# licthla.net
KiCad netlist of a schematic drawn in EAGLE
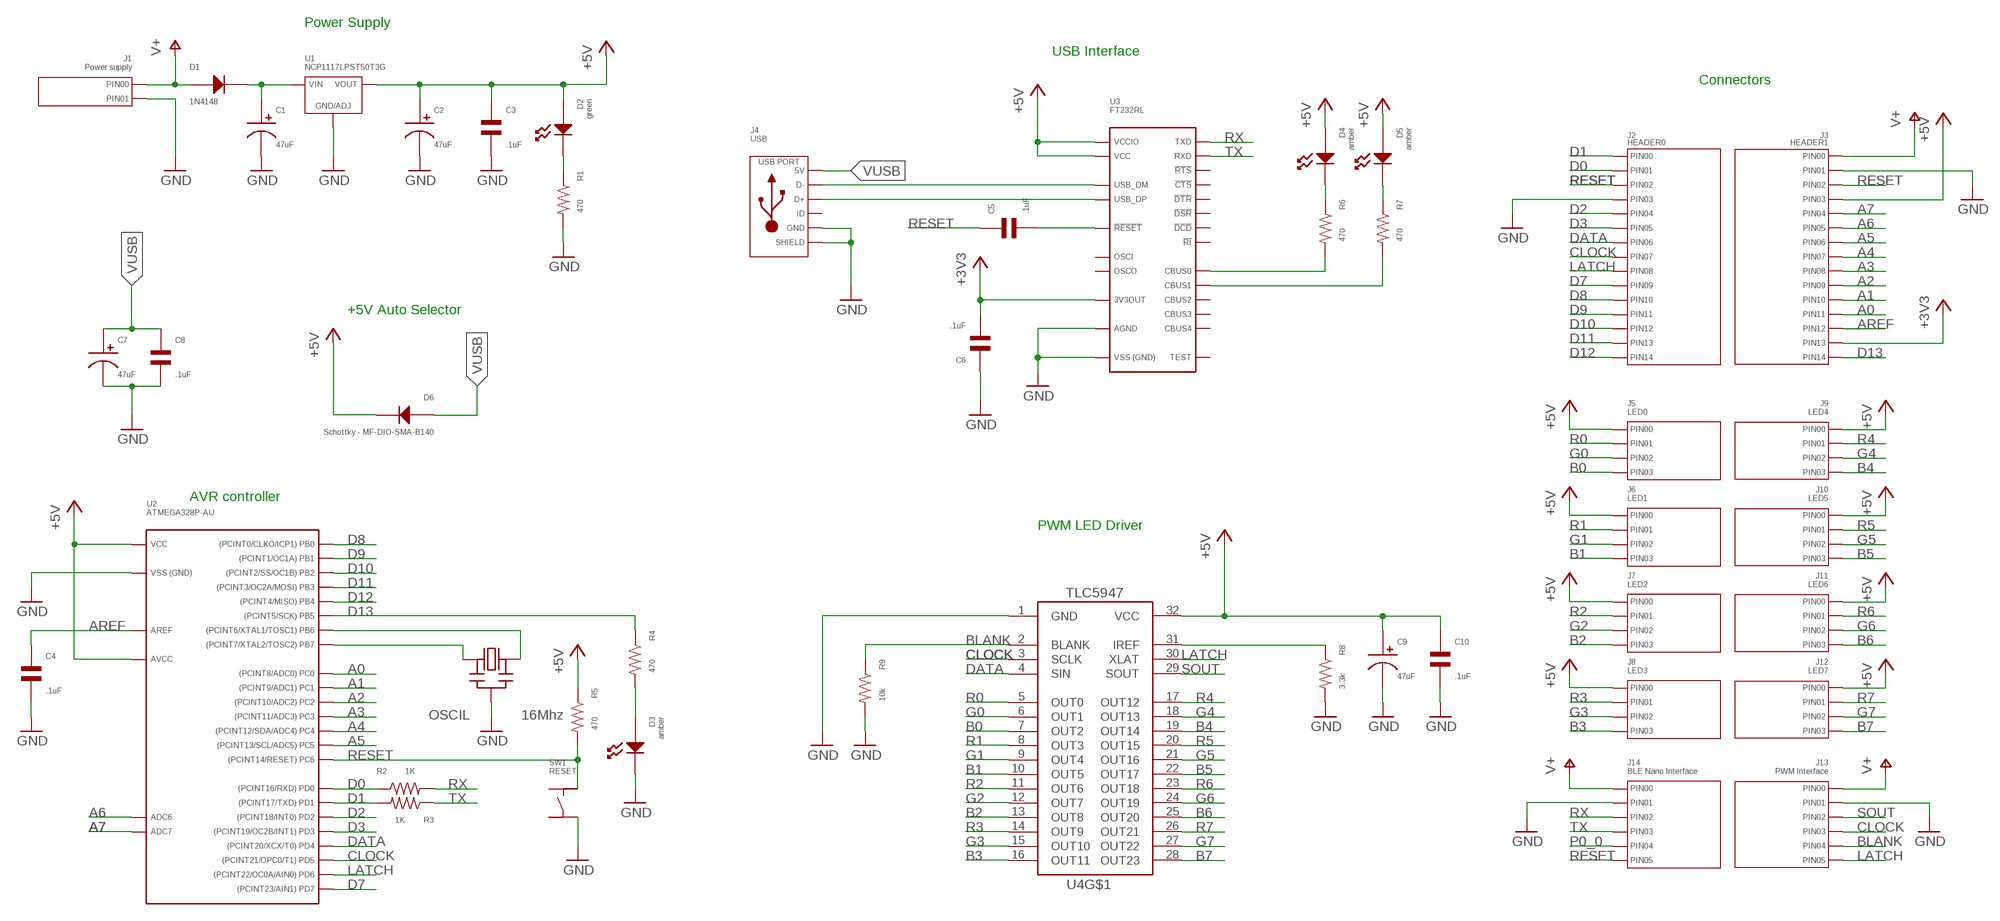
[diagram p0: schematic, sheet 1]

(export (version "E")
  (design (tool "Eeschema 10.0.6"))
  (components
    (comp (ref "C1")
      (value "47uF")
      (footprint "eagle-import:CP6.3MM")
      (libsource (lib "eagle-import") (part "CAPACITOR_P_6.3MM"))
    )
    (comp (ref "C2")
      (value "47uF")
      (footprint "eagle-import:CP6.3MM")
      (libsource (lib "eagle-import") (part "CAPACITOR_P_6.3MM"))
    )
    (comp (ref "C3")
      (value ".1uF")
      (footprint "eagle-import:C0402")
      (libsource (lib "eagle-import") (part "CAPACITOR_NP_0402"))
    )
    (comp (ref "C4")
      (value ".1uF")
      (footprint "eagle-import:C0402")
      (libsource (lib "eagle-import") (part "CAPACITOR_NP_0402"))
    )
    (comp (ref "C5")
      (value ".1uF")
      (footprint "eagle-import:C0402")
      (libsource (lib "eagle-import") (part "CAPACITOR_NP_0402"))
    )
    (comp (ref "C6")
      (value ".1uF")
      (footprint "eagle-import:C0402")
      (libsource (lib "eagle-import") (part "CAPACITOR_NP_0402"))
    )
    (comp (ref "C7")
      (value "47uF")
      (footprint "eagle-import:CP6.3MM")
      (libsource (lib "eagle-import") (part "CAPACITOR_P_6.3MM"))
    )
    (comp (ref "C8")
      (value ".1uF")
      (footprint "eagle-import:C0402")
      (libsource (lib "eagle-import") (part "CAPACITOR_NP_0402"))
    )
    (comp (ref "C9")
      (value "47uF")
      (footprint "eagle-import:CP6.3MM")
      (libsource (lib "eagle-import") (part "CAPACITOR_P_6.3MM"))
    )
    (comp (ref "C10")
      (value ".1uF")
      (footprint "eagle-import:C0402")
      (libsource (lib "eagle-import") (part "CAPACITOR_NP_0402"))
    )
    (comp (ref "D1")
      (value "1N4148")
      (footprint "eagle-import:SOD-123")
      (libsource (lib "eagle-import") (part "DIODE_SOD-123"))
    )
    (comp (ref "D2")
      (value "green")
      (footprint "eagle-import:LED0805")
      (libsource (lib "eagle-import") (part "LED_SINGLE_0805"))
    )
    (comp (ref "D3")
      (value "amber")
      (footprint "eagle-import:LED0805")
      (libsource (lib "eagle-import") (part "LED_SINGLE_0805"))
    )
    (comp (ref "D4")
      (value "amber")
      (footprint "eagle-import:LED0805")
      (libsource (lib "eagle-import") (part "LED_SINGLE_0805"))
    )
    (comp (ref "D5")
      (value "amber")
      (footprint "eagle-import:LED0805")
      (libsource (lib "eagle-import") (part "LED_SINGLE_0805"))
    )
    (comp (ref "D6")
      (value "Schottky - MF-DIO-SMA-B140")
      (footprint "eagle-import:SMA")
      (libsource (lib "eagle-import") (part "DIODE_SMA"))
    )
    (comp (ref "J1")
      (value "Power supply")
      (footprint "eagle-import:PTH_2.54MM_01X02")
      (libsource (lib "eagle-import") (part "HEADER_01X02_PTH_2.54MM"))
    )
    (comp (ref "J2")
      (value "HEADER0")
      (footprint "eagle-import:PTH_2.54MM_01X15")
      (libsource (lib "eagle-import") (part "HEADER_01X15_PTH_2.54MM"))
    )
    (comp (ref "J3")
      (value "HEADER1")
      (footprint "eagle-import:PTH_2.54MM_01X15")
      (libsource (lib "eagle-import") (part "HEADER_01X15_PTH_2.54MM"))
    )
    (comp (ref "J4")
      (value "USB")
      (footprint "eagle-import:MICROUSB-RIGHT")
      (libsource (lib "eagle-import") (part "USB_MICRO_RIGHT"))
    )
    (comp (ref "J5")
      (value "LED0")
      (footprint "eagle-import:PTH_2.54MM_01X04")
      (libsource (lib "eagle-import") (part "HEADER_01X04_PTH_2.54MM"))
    )
    (comp (ref "J6")
      (value "LED1")
      (footprint "eagle-import:PTH_2.54MM_01X04")
      (libsource (lib "eagle-import") (part "HEADER_01X04_PTH_2.54MM"))
    )
    (comp (ref "J7")
      (value "LED2")
      (footprint "eagle-import:PTH_2.54MM_01X04")
      (libsource (lib "eagle-import") (part "HEADER_01X04_PTH_2.54MM"))
    )
    (comp (ref "J8")
      (value "LED3")
      (footprint "eagle-import:PTH_2.54MM_01X04")
      (libsource (lib "eagle-import") (part "HEADER_01X04_PTH_2.54MM"))
    )
    (comp (ref "J9")
      (value "LED4")
      (footprint "eagle-import:PTH_2.54MM_01X04")
      (libsource (lib "eagle-import") (part "HEADER_01X04_PTH_2.54MM"))
    )
    (comp (ref "J10")
      (value "LED5")
      (footprint "eagle-import:PTH_2.54MM_01X04")
      (libsource (lib "eagle-import") (part "HEADER_01X04_PTH_2.54MM"))
    )
    (comp (ref "J11")
      (value "LED6")
      (footprint "eagle-import:PTH_2.54MM_01X04")
      (libsource (lib "eagle-import") (part "HEADER_01X04_PTH_2.54MM"))
    )
    (comp (ref "J12")
      (value "LED7")
      (footprint "eagle-import:PTH_2.54MM_01X04")
      (libsource (lib "eagle-import") (part "HEADER_01X04_PTH_2.54MM"))
    )
    (comp (ref "J13")
      (value "PWM Interface")
      (footprint "eagle-import:PTH_2.54MM_01X06")
      (libsource (lib "eagle-import") (part "HEADER_01X06_PTH_2.54MM"))
    )
    (comp (ref "J14")
      (value "BLE Nano Interface")
      (footprint "eagle-import:PTH_2.54MM_01X06")
      (libsource (lib "eagle-import") (part "HEADER_01X06_PTH_2.54MM"))
    )
    (comp (ref "OSCIL")
      (value "16Mhz")
      (footprint "eagle-import:AWCSR")
      (libsource (lib "eagle-import") (part "CERMOSCILL-AWCSR"))
    )
    (comp (ref "R1")
      (value "470")
      (footprint "eagle-import:R0805")
      (libsource (lib "eagle-import") (part "RESISTOR_0805"))
    )
    (comp (ref "R2")
      (value "1K")
      (footprint "eagle-import:R0805")
      (libsource (lib "eagle-import") (part "RESISTOR_0805"))
    )
    (comp (ref "R3")
      (value "1K")
      (footprint "eagle-import:R0805")
      (libsource (lib "eagle-import") (part "RESISTOR_0805"))
    )
    (comp (ref "R4")
      (value "470")
      (footprint "eagle-import:R0805")
      (libsource (lib "eagle-import") (part "RESISTOR_0805"))
    )
    (comp (ref "R5")
      (value "470")
      (footprint "eagle-import:R0805")
      (libsource (lib "eagle-import") (part "RESISTOR_0805"))
    )
    (comp (ref "R6")
      (value "470")
      (footprint "eagle-import:R0805")
      (libsource (lib "eagle-import") (part "RESISTOR_0805"))
    )
    (comp (ref "R7")
      (value "470")
      (footprint "eagle-import:R0805")
      (libsource (lib "eagle-import") (part "RESISTOR_0805"))
    )
    (comp (ref "R8")
      (value "3.3k")
      (footprint "eagle-import:R0805")
      (libsource (lib "eagle-import") (part "RESISTOR_0805"))
    )
    (comp (ref "R9")
      (value "10k")
      (footprint "eagle-import:R0805")
      (libsource (lib "eagle-import") (part "RESISTOR_0805"))
    )
    (comp (ref "SW1")
      (value "RESET")
      (footprint "eagle-import:TACT6MM")
      (libsource (lib "eagle-import") (part "TACT_6MM"))
    )
    (comp (ref "U1")
      (value "NCP1117LPST50T3G")
      (footprint "eagle-import:SOT-223-3")
      (libsource (lib "eagle-import") (part "NCP1117LPST50T3G"))
    )
    (comp (ref "U2")
      (value "ATMEGA328P-AU")
      (footprint "eagle-import:TQFP32")
      (libsource (lib "eagle-import") (part "ATMEGA328P-AU"))
    )
    (comp (ref "U3")
      (value "FT232RL")
      (footprint "eagle-import:SSOP28")
      (libsource (lib "eagle-import") (part "FT232RL"))
    )
    (comp (ref "U4")
      (value "TLC5947-DAP")
      (footprint "eagle-import:HTSSOP32DAP")
      (libsource (lib "eagle-import") (part "TLC5947-DAP"))
    )
  )
  (nets
    (net (code "1") (name "+3V3") (class "Default")
      (node (ref "C6") (pin "P$2") (pinfunction "P$2_P$2") (pintype "passive"))
      (node (ref "J3") (pin "P$14") (pinfunction "PIN13_P$14") (pintype "bidirectional"))
      (node (ref "U3") (pin "P$17") (pinfunction "3V3OUT_P$17") (pintype "bidirectional"))
    )
    (net (code "2") (name "+5V") (class "Default")
      (node (ref "C10") (pin "P$1") (pinfunction "P$1_P$1") (pintype "passive"))
      (node (ref "C2") (pin "P$1") (pinfunction "P$1_P$1") (pintype "passive"))
      (node (ref "C3") (pin "P$1") (pinfunction "P$1_P$1") (pintype "passive"))
      (node (ref "C9") (pin "P$1") (pinfunction "P$1_P$1") (pintype "passive"))
      (node (ref "D2") (pin "ANODE") (pinfunction "ANODE_ANODE") (pintype "power_in"))
      (node (ref "D4") (pin "ANODE") (pinfunction "ANODE_ANODE") (pintype "power_in"))
      (node (ref "D5") (pin "ANODE") (pinfunction "ANODE_ANODE") (pintype "power_in"))
      (node (ref "D6") (pin "CATHODE") (pinfunction "CATHODE_CATHODE") (pintype "bidirectional"))
      (node (ref "J10") (pin "P$1") (pinfunction "PIN0_P$1") (pintype "bidirectional"))
      (node (ref "J11") (pin "P$1") (pinfunction "PIN0_P$1") (pintype "bidirectional"))
      (node (ref "J12") (pin "P$1") (pinfunction "PIN0_P$1") (pintype "bidirectional"))
      (node (ref "J3") (pin "P$4") (pinfunction "PIN3_P$4") (pintype "bidirectional"))
      (node (ref "J5") (pin "P$1") (pinfunction "PIN0_P$1") (pintype "bidirectional"))
      (node (ref "J6") (pin "P$1") (pinfunction "PIN0_P$1") (pintype "bidirectional"))
      (node (ref "J7") (pin "P$1") (pinfunction "PIN0_P$1") (pintype "bidirectional"))
      (node (ref "J8") (pin "P$1") (pinfunction "PIN0_P$1") (pintype "bidirectional"))
      (node (ref "J9") (pin "P$1") (pinfunction "PIN0_P$1") (pintype "bidirectional"))
      (node (ref "R5") (pin "P$1") (pinfunction "P$1_P$1") (pintype "passive"))
      (node (ref "U1") (pin "P$1") (pinfunction "VOUT_P$1") (pintype "bidirectional"))
      (node (ref "U1") (pin "P$3") (pinfunction "VOUT_P$3") (pintype "bidirectional"))
      (node (ref "U2") (pin "P$18") (pinfunction "AVCC_P$18") (pintype "power_in"))
      (node (ref "U2") (pin "P$4") (pinfunction "VCC_P$4") (pintype "power_in"))
      (node (ref "U2") (pin "P$6") (pinfunction "VCC_P$6") (pintype "power_in"))
      (node (ref "U3") (pin "P$20") (pinfunction "VCC_P$20") (pintype "bidirectional"))
      (node (ref "U3") (pin "P$4") (pinfunction "VCCIO_P$4") (pintype "bidirectional"))
      (node (ref "U4") (pin "32") (pinfunction "VCC_32") (pintype "power_in"))
    )
    (net (code "3") (name "/A0") (class "Default")
      (node (ref "J3") (pin "P$12") (pinfunction "PIN11_P$12") (pintype "bidirectional"))
      (node (ref "U2") (pin "P$23") (pinfunction "PC0_P$23") (pintype "bidirectional"))
    )
    (net (code "4") (name "/A1") (class "Default")
      (node (ref "J3") (pin "P$11") (pinfunction "PIN10_P$11") (pintype "bidirectional"))
      (node (ref "U2") (pin "P$24") (pinfunction "PC1_P$24") (pintype "bidirectional"))
    )
    (net (code "5") (name "/A2") (class "Default")
      (node (ref "J3") (pin "P$10") (pinfunction "PIN9_P$10") (pintype "bidirectional"))
      (node (ref "U2") (pin "P$25") (pinfunction "PC2_P$25") (pintype "bidirectional"))
    )
    (net (code "6") (name "/A3") (class "Default")
      (node (ref "J3") (pin "P$9") (pinfunction "PIN8_P$9") (pintype "bidirectional"))
      (node (ref "U2") (pin "P$26") (pinfunction "PC3_P$26") (pintype "bidirectional"))
    )
    (net (code "7") (name "/A4") (class "Default")
      (node (ref "J3") (pin "P$8") (pinfunction "PIN7_P$8") (pintype "bidirectional"))
      (node (ref "U2") (pin "P$27") (pinfunction "PC4_P$27") (pintype "bidirectional"))
    )
    (net (code "8") (name "/A5") (class "Default")
      (node (ref "J3") (pin "P$7") (pinfunction "PIN6_P$7") (pintype "bidirectional"))
      (node (ref "U2") (pin "P$28") (pinfunction "PC5_P$28") (pintype "bidirectional"))
    )
    (net (code "9") (name "/A6") (class "Default")
      (node (ref "J3") (pin "P$6") (pinfunction "PIN5_P$6") (pintype "bidirectional"))
      (node (ref "U2") (pin "P$19") (pinfunction "ADC6_P$19") (pintype "bidirectional"))
    )
    (net (code "10") (name "/A7") (class "Default")
      (node (ref "J3") (pin "P$5") (pinfunction "PIN4_P$5") (pintype "bidirectional"))
      (node (ref "U2") (pin "P$22") (pinfunction "ADC7_P$22") (pintype "bidirectional"))
    )
    (net (code "11") (name "/AREF") (class "Default")
      (node (ref "C4") (pin "P$1") (pinfunction "P$1_P$1") (pintype "passive"))
      (node (ref "J3") (pin "P$13") (pinfunction "PIN12_P$13") (pintype "bidirectional"))
      (node (ref "U2") (pin "P$20") (pinfunction "AREF_P$20") (pintype "power_in"))
    )
    (net (code "12") (name "/B0") (class "Default")
      (node (ref "J5") (pin "P$4") (pinfunction "PIN3_P$4") (pintype "bidirectional"))
      (node (ref "U4") (pin "7") (pinfunction "OUT2_7") (pintype "open_collector"))
    )
    (net (code "13") (name "/B1") (class "Default")
      (node (ref "J6") (pin "P$4") (pinfunction "PIN3_P$4") (pintype "bidirectional"))
      (node (ref "U4") (pin "10") (pinfunction "OUT5_10") (pintype "open_collector"))
    )
    (net (code "14") (name "/B2") (class "Default")
      (node (ref "J7") (pin "P$4") (pinfunction "PIN3_P$4") (pintype "bidirectional"))
      (node (ref "U4") (pin "13") (pinfunction "OUT8_13") (pintype "open_collector"))
    )
    (net (code "15") (name "/B3") (class "Default")
      (node (ref "J8") (pin "P$4") (pinfunction "PIN3_P$4") (pintype "bidirectional"))
      (node (ref "U4") (pin "16") (pinfunction "OUT11_16") (pintype "open_collector"))
    )
    (net (code "16") (name "/B4") (class "Default")
      (node (ref "J9") (pin "P$4") (pinfunction "PIN3_P$4") (pintype "bidirectional"))
      (node (ref "U4") (pin "19") (pinfunction "OUT14_19") (pintype "open_collector"))
    )
    (net (code "17") (name "/B5") (class "Default")
      (node (ref "J10") (pin "P$4") (pinfunction "PIN3_P$4") (pintype "bidirectional"))
      (node (ref "U4") (pin "22") (pinfunction "OUT17_22") (pintype "open_collector"))
    )
    (net (code "18") (name "/B6") (class "Default")
      (node (ref "J11") (pin "P$4") (pinfunction "PIN3_P$4") (pintype "bidirectional"))
      (node (ref "U4") (pin "25") (pinfunction "OUT20_25") (pintype "open_collector"))
    )
    (net (code "19") (name "/B7") (class "Default")
      (node (ref "J12") (pin "P$4") (pinfunction "PIN3_P$4") (pintype "bidirectional"))
      (node (ref "U4") (pin "28") (pinfunction "OUT23_28") (pintype "open_collector"))
    )
    (net (code "20") (name "/BLANK") (class "Default")
      (node (ref "J13") (pin "P$5") (pinfunction "PIN4_P$5") (pintype "bidirectional"))
      (node (ref "R9") (pin "P$1") (pinfunction "P$1_P$1") (pintype "passive"))
      (node (ref "U4") (pin "2") (pinfunction "BLANK_2") (pintype "input"))
    )
    (net (code "21") (name "/CLOCK") (class "Default")
      (node (ref "J13") (pin "P$4") (pinfunction "PIN3_P$4") (pintype "bidirectional"))
      (node (ref "J2") (pin "P$8") (pinfunction "PIN7_P$8") (pintype "bidirectional"))
      (node (ref "U2") (pin "P$9") (pinfunction "PD5_P$9") (pintype "bidirectional"))
      (node (ref "U4") (pin "3") (pinfunction "SCLK_3") (pintype "input"))
    )
    (net (code "22") (name "/D0") (class "Default")
      (node (ref "J2") (pin "P$2") (pinfunction "PIN1_P$2") (pintype "bidirectional"))
      (node (ref "R2") (pin "P$1") (pinfunction "P$1_P$1") (pintype "passive"))
      (node (ref "U2") (pin "P$30") (pinfunction "PD0_P$30") (pintype "bidirectional"))
    )
    (net (code "23") (name "/D1") (class "Default")
      (node (ref "J2") (pin "P$1") (pinfunction "PIN0_P$1") (pintype "bidirectional"))
      (node (ref "R3") (pin "P$2") (pinfunction "P$2_P$2") (pintype "passive"))
      (node (ref "U2") (pin "P$31") (pinfunction "PD1_P$31") (pintype "bidirectional"))
    )
    (net (code "24") (name "/D2") (class "Default")
      (node (ref "J2") (pin "P$5") (pinfunction "PIN4_P$5") (pintype "bidirectional"))
      (node (ref "U2") (pin "P$32") (pinfunction "PD2_P$32") (pintype "bidirectional"))
    )
    (net (code "25") (name "/D3") (class "Default")
      (node (ref "J2") (pin "P$6") (pinfunction "PIN5_P$6") (pintype "bidirectional"))
      (node (ref "U2") (pin "P$1") (pinfunction "PD3_P$1") (pintype "bidirectional"))
    )
    (net (code "26") (name "/D7") (class "Default")
      (node (ref "J2") (pin "P$10") (pinfunction "PIN9_P$10") (pintype "bidirectional"))
      (node (ref "U2") (pin "P$11") (pinfunction "PD7_P$11") (pintype "bidirectional"))
    )
    (net (code "27") (name "/D8") (class "Default")
      (node (ref "J2") (pin "P$11") (pinfunction "PIN10_P$11") (pintype "bidirectional"))
      (node (ref "U2") (pin "P$12") (pinfunction "PB0_P$12") (pintype "bidirectional"))
    )
    (net (code "28") (name "/D9") (class "Default")
      (node (ref "J2") (pin "P$12") (pinfunction "PIN11_P$12") (pintype "bidirectional"))
      (node (ref "U2") (pin "P$13") (pinfunction "PB1_P$13") (pintype "bidirectional"))
    )
    (net (code "29") (name "/D10") (class "Default")
      (node (ref "J2") (pin "P$13") (pinfunction "PIN12_P$13") (pintype "bidirectional"))
      (node (ref "U2") (pin "P$14") (pinfunction "PB2_P$14") (pintype "bidirectional"))
    )
    (net (code "30") (name "/D11") (class "Default")
      (node (ref "J2") (pin "P$14") (pinfunction "PIN13_P$14") (pintype "bidirectional"))
      (node (ref "U2") (pin "P$15") (pinfunction "PB3_P$15") (pintype "bidirectional"))
    )
    (net (code "31") (name "/D12") (class "Default")
      (node (ref "J2") (pin "P$15") (pinfunction "PIN14_P$15") (pintype "bidirectional"))
      (node (ref "U2") (pin "P$16") (pinfunction "PB4_P$16") (pintype "bidirectional"))
    )
    (net (code "32") (name "/D13") (class "Default")
      (node (ref "J3") (pin "P$15") (pinfunction "PIN14_P$15") (pintype "bidirectional"))
      (node (ref "R4") (pin "P$1") (pinfunction "P$1_P$1") (pintype "passive"))
      (node (ref "U2") (pin "P$17") (pinfunction "PB5_P$17") (pintype "bidirectional"))
    )
    (net (code "33") (name "/DATA") (class "Default")
      (node (ref "J2") (pin "P$7") (pinfunction "PIN6_P$7") (pintype "bidirectional"))
      (node (ref "U2") (pin "P$2") (pinfunction "PD4_P$2") (pintype "bidirectional"))
      (node (ref "U4") (pin "4") (pinfunction "SIN_4") (pintype "input"))
    )
    (net (code "34") (name "/G0") (class "Default")
      (node (ref "J5") (pin "P$3") (pinfunction "PIN2_P$3") (pintype "bidirectional"))
      (node (ref "U4") (pin "6") (pinfunction "OUT1_6") (pintype "open_collector"))
    )
    (net (code "35") (name "/G1") (class "Default")
      (node (ref "J6") (pin "P$3") (pinfunction "PIN2_P$3") (pintype "bidirectional"))
      (node (ref "U4") (pin "9") (pinfunction "OUT4_9") (pintype "open_collector"))
    )
    (net (code "36") (name "/G2") (class "Default")
      (node (ref "J7") (pin "P$3") (pinfunction "PIN2_P$3") (pintype "bidirectional"))
      (node (ref "U4") (pin "12") (pinfunction "OUT7_12") (pintype "open_collector"))
    )
    (net (code "37") (name "/G3") (class "Default")
      (node (ref "J8") (pin "P$3") (pinfunction "PIN2_P$3") (pintype "bidirectional"))
      (node (ref "U4") (pin "15") (pinfunction "OUT10_15") (pintype "open_collector"))
    )
    (net (code "38") (name "/G4") (class "Default")
      (node (ref "J9") (pin "P$3") (pinfunction "PIN2_P$3") (pintype "bidirectional"))
      (node (ref "U4") (pin "18") (pinfunction "OUT13_18") (pintype "open_collector"))
    )
    (net (code "39") (name "/G5") (class "Default")
      (node (ref "J10") (pin "P$3") (pinfunction "PIN2_P$3") (pintype "bidirectional"))
      (node (ref "U4") (pin "21") (pinfunction "OUT16_21") (pintype "open_collector"))
    )
    (net (code "40") (name "/G6") (class "Default")
      (node (ref "J11") (pin "P$3") (pinfunction "PIN2_P$3") (pintype "bidirectional"))
      (node (ref "U4") (pin "24") (pinfunction "OUT19_24") (pintype "open_collector"))
    )
    (net (code "41") (name "/G7") (class "Default")
      (node (ref "J12") (pin "P$3") (pinfunction "PIN2_P$3") (pintype "bidirectional"))
      (node (ref "U4") (pin "27") (pinfunction "OUT22_27") (pintype "open_collector"))
    )
    (net (code "42") (name "/LATCH") (class "Default")
      (node (ref "J13") (pin "P$6") (pinfunction "PIN5_P$6") (pintype "bidirectional"))
      (node (ref "J2") (pin "P$9") (pinfunction "PIN8_P$9") (pintype "bidirectional"))
      (node (ref "U2") (pin "P$10") (pinfunction "PD6_P$10") (pintype "bidirectional"))
      (node (ref "U4") (pin "30") (pinfunction "XLAT_30") (pintype "input"))
    )
    (net (code "43") (name "/P0_0") (class "Default")
      (node (ref "J14") (pin "P$5") (pinfunction "PIN4_P$5") (pintype "bidirectional"))
    )
    (net (code "44") (name "/R0") (class "Default")
      (node (ref "J5") (pin "P$2") (pinfunction "PIN1_P$2") (pintype "bidirectional"))
      (node (ref "U4") (pin "5") (pinfunction "OUT0_5") (pintype "open_collector"))
    )
    (net (code "45") (name "/R1") (class "Default")
      (node (ref "J6") (pin "P$2") (pinfunction "PIN1_P$2") (pintype "bidirectional"))
      (node (ref "U4") (pin "8") (pinfunction "OUT3_8") (pintype "open_collector"))
    )
    (net (code "46") (name "/R2") (class "Default")
      (node (ref "J7") (pin "P$2") (pinfunction "PIN1_P$2") (pintype "bidirectional"))
      (node (ref "U4") (pin "11") (pinfunction "OUT6_11") (pintype "open_collector"))
    )
    (net (code "47") (name "/R3") (class "Default")
      (node (ref "J8") (pin "P$2") (pinfunction "PIN1_P$2") (pintype "bidirectional"))
      (node (ref "U4") (pin "14") (pinfunction "OUT9_14") (pintype "open_collector"))
    )
    (net (code "48") (name "/R4") (class "Default")
      (node (ref "J9") (pin "P$2") (pinfunction "PIN1_P$2") (pintype "bidirectional"))
      (node (ref "U4") (pin "17") (pinfunction "OUT12_17") (pintype "open_collector"))
    )
    (net (code "49") (name "/R5") (class "Default")
      (node (ref "J10") (pin "P$2") (pinfunction "PIN1_P$2") (pintype "bidirectional"))
      (node (ref "U4") (pin "20") (pinfunction "OUT15_20") (pintype "open_collector"))
    )
    (net (code "50") (name "/R6") (class "Default")
      (node (ref "J11") (pin "P$2") (pinfunction "PIN1_P$2") (pintype "bidirectional"))
      (node (ref "U4") (pin "23") (pinfunction "OUT18_23") (pintype "open_collector"))
    )
    (net (code "51") (name "/R7") (class "Default")
      (node (ref "J12") (pin "P$2") (pinfunction "PIN1_P$2") (pintype "bidirectional"))
      (node (ref "U4") (pin "26") (pinfunction "OUT21_26") (pintype "open_collector"))
    )
    (net (code "52") (name "/RESET") (class "Default")
      (node (ref "C5") (pin "P$1") (pinfunction "P$1_P$1") (pintype "passive"))
      (node (ref "J14") (pin "P$6") (pinfunction "PIN5_P$6") (pintype "bidirectional"))
      (node (ref "J2") (pin "P$3") (pinfunction "PIN2_P$3") (pintype "bidirectional"))
      (node (ref "J3") (pin "P$3") (pinfunction "PIN2_P$3") (pintype "bidirectional"))
      (node (ref "R5") (pin "P$2") (pinfunction "P$2_P$2") (pintype "passive"))
      (node (ref "SW1") (pin "P$2") (pinfunction "P$2_P$2") (pintype "bidirectional"))
      (node (ref "U2") (pin "P$29") (pinfunction "PC6_P$29") (pintype "bidirectional"))
    )
    (net (code "53") (name "/RX") (class "Default")
      (node (ref "J14") (pin "P$3") (pinfunction "PIN2_P$3") (pintype "bidirectional"))
      (node (ref "R2") (pin "P$2") (pinfunction "P$2_P$2") (pintype "passive"))
      (node (ref "U3") (pin "P$1") (pinfunction "TXD_P$1") (pintype "bidirectional"))
    )
    (net (code "54") (name "/SOUT") (class "Default")
      (node (ref "J13") (pin "P$3") (pinfunction "PIN2_P$3") (pintype "bidirectional"))
      (node (ref "U4") (pin "29") (pinfunction "SOUT_29") (pintype "output"))
    )
    (net (code "55") (name "/TX") (class "Default")
      (node (ref "J14") (pin "P$4") (pinfunction "PIN3_P$4") (pintype "bidirectional"))
      (node (ref "R3") (pin "P$1") (pinfunction "P$1_P$1") (pintype "passive"))
      (node (ref "U3") (pin "P$5") (pinfunction "RXD_P$5") (pintype "bidirectional"))
    )
    (net (code "56") (name "GND") (class "Default")
      (node (ref "C1") (pin "P$2") (pinfunction "P$2_P$2") (pintype "passive"))
      (node (ref "C10") (pin "P$2") (pinfunction "P$2_P$2") (pintype "passive"))
      (node (ref "C2") (pin "P$2") (pinfunction "P$2_P$2") (pintype "passive"))
      (node (ref "C3") (pin "P$2") (pinfunction "P$2_P$2") (pintype "passive"))
      (node (ref "C4") (pin "P$2") (pinfunction "P$2_P$2") (pintype "passive"))
      (node (ref "C6") (pin "P$1") (pinfunction "P$1_P$1") (pintype "passive"))
      (node (ref "C7") (pin "P$2") (pinfunction "P$2_P$2") (pintype "passive"))
      (node (ref "C8") (pin "P$2") (pinfunction "P$2_P$2") (pintype "passive"))
      (node (ref "C9") (pin "P$2") (pinfunction "P$2_P$2") (pintype "passive"))
      (node (ref "D3") (pin "CATHODE") (pinfunction "CATHODE_CATHODE") (pintype "power_in"))
      (node (ref "J1") (pin "P$1") (pinfunction "PIN1_P$1") (pintype "bidirectional"))
      (node (ref "J13") (pin "P$2") (pinfunction "PIN1_P$2") (pintype "bidirectional"))
      (node (ref "J14") (pin "P$2") (pinfunction "PIN1_P$2") (pintype "bidirectional"))
      (node (ref "J2") (pin "P$4") (pinfunction "PIN3_P$4") (pintype "bidirectional"))
      (node (ref "J3") (pin "P$2") (pinfunction "PIN1_P$2") (pintype "bidirectional"))
      (node (ref "J4") (pin "5") (pinfunction "GND_5") (pintype "power_in"))
      (node (ref "J4") (pin "S1") (pinfunction "SLD_S1") (pintype "power_in"))
      (node (ref "J4") (pin "S2") (pinfunction "SLD_S2") (pintype "power_in"))
      (node (ref "J4") (pin "S3") (pinfunction "SLD_S3") (pintype "power_in"))
      (node (ref "J4") (pin "S4") (pinfunction "SLD_S4") (pintype "power_in"))
      (node (ref "J4") (pin "S5") (pinfunction "SLD_S5") (pintype "power_in"))
      (node (ref "J4") (pin "S6") (pinfunction "SLD_S6") (pintype "power_in"))
      (node (ref "J4") (pin "S7") (pinfunction "SLD_S7") (pintype "power_in"))
      (node (ref "J4") (pin "S8") (pinfunction "SLD_S8") (pintype "power_in"))
      (node (ref "OSCIL") (pin "2") (pinfunction "GND_2") (pintype "bidirectional"))
      (node (ref "R1") (pin "P$2") (pinfunction "P$2_P$2") (pintype "passive"))
      (node (ref "R8") (pin "P$2") (pinfunction "P$2_P$2") (pintype "passive"))
      (node (ref "R9") (pin "P$2") (pinfunction "P$2_P$2") (pintype "passive"))
      (node (ref "SW1") (pin "P$4") (pinfunction "P$4_P$4") (pintype "bidirectional"))
      (node (ref "U1") (pin "P$2") (pinfunction "GND/ADJ_P$2") (pintype "bidirectional"))
      (node (ref "U2") (pin "P$21") (pinfunction "GND_P$21") (pintype "power_in"))
      (node (ref "U2") (pin "P$3") (pinfunction "GND_P$3") (pintype "power_in"))
      (node (ref "U2") (pin "P$5") (pinfunction "GND_P$5") (pintype "power_in"))
      (node (ref "U3") (pin "P$18") (pinfunction "GND_P$18") (pintype "bidirectional"))
      (node (ref "U3") (pin "P$21") (pinfunction "GND_P$21") (pintype "bidirectional"))
      (node (ref "U3") (pin "P$25") (pinfunction "AGND_P$25") (pintype "bidirectional"))
      (node (ref "U3") (pin "P$7") (pinfunction "GND_P$7") (pintype "bidirectional"))
      (node (ref "U4") (pin "1") (pinfunction "GND_1") (pintype "power_in"))
    )
    (net (code "57") (name "Net-(D2-PadCATHODE)") (class "Default")
      (node (ref "D2") (pin "CATHODE") (pinfunction "CATHODE_CATHODE") (pintype "power_in"))
      (node (ref "R1") (pin "P$1") (pinfunction "P$1_P$1") (pintype "passive"))
    )
    (net (code "58") (name "Net-(D3-PadANODE)") (class "Default")
      (node (ref "D3") (pin "ANODE") (pinfunction "ANODE_ANODE") (pintype "power_in"))
      (node (ref "R4") (pin "P$2") (pinfunction "P$2_P$2") (pintype "passive"))
    )
    (net (code "59") (name "Net-(D4-PadCATHODE)") (class "Default")
      (node (ref "D4") (pin "CATHODE") (pinfunction "CATHODE_CATHODE") (pintype "power_in"))
      (node (ref "R6") (pin "P$1") (pinfunction "P$1_P$1") (pintype "passive"))
    )
    (net (code "60") (name "Net-(D5-PadCATHODE)") (class "Default")
      (node (ref "D5") (pin "CATHODE") (pinfunction "CATHODE_CATHODE") (pintype "power_in"))
      (node (ref "R7") (pin "P$1") (pinfunction "P$1_P$1") (pintype "passive"))
    )
    (net (code "61") (name "Net-(J4-D+)") (class "Default")
      (node (ref "J4") (pin "3") (pinfunction "D+_3") (pintype "bidirectional"))
      (node (ref "U3") (pin "P$15") (pinfunction "USBDP_P$15") (pintype "bidirectional"))
    )
    (net (code "62") (name "Net-(J4-D-)") (class "Default")
      (node (ref "J4") (pin "2") (pinfunction "D-_2") (pintype "bidirectional"))
      (node (ref "U3") (pin "P$16") (pinfunction "USBDM_P$16") (pintype "bidirectional"))
    )
    (net (code "63") (name "Net-(OSCIL-IN)") (class "Default")
      (node (ref "OSCIL") (pin "1") (pinfunction "IN_1") (pintype "bidirectional"))
      (node (ref "U2") (pin "P$8") (pinfunction "PB7_P$8") (pintype "bidirectional"))
    )
    (net (code "64") (name "Net-(OSCIL-OUT)") (class "Default")
      (node (ref "OSCIL") (pin "3") (pinfunction "OUT_3") (pintype "bidirectional"))
      (node (ref "U2") (pin "P$7") (pinfunction "PB6_P$7") (pintype "bidirectional"))
    )
    (net (code "65") (name "Net-(U1-VIN)") (class "Default")
      (node (ref "C1") (pin "P$1") (pinfunction "P$1_P$1") (pintype "passive"))
      (node (ref "D1") (pin "CATHODE") (pinfunction "CATHODE_CATHODE") (pintype "bidirectional"))
      (node (ref "U1") (pin "P$4") (pinfunction "VIN_P$4") (pintype "bidirectional"))
    )
    (net (code "66") (name "Net-(U3-CBUS0)") (class "Default")
      (node (ref "R6") (pin "P$2") (pinfunction "P$2_P$2") (pintype "passive"))
      (node (ref "U3") (pin "P$23") (pinfunction "CBUS0_P$23") (pintype "bidirectional"))
    )
    (net (code "67") (name "Net-(U3-CBUS1)") (class "Default")
      (node (ref "R7") (pin "P$2") (pinfunction "P$2_P$2") (pintype "passive"))
      (node (ref "U3") (pin "P$22") (pinfunction "CBUS1_P$22") (pintype "bidirectional"))
    )
    (net (code "68") (name "Net-(U3-~{RESET})") (class "Default")
      (node (ref "C5") (pin "P$2") (pinfunction "P$2_P$2") (pintype "passive"))
      (node (ref "U3") (pin "P$19") (pinfunction "~{RESET}_P$19") (pintype "bidirectional"))
    )
    (net (code "69") (name "Net-(U4A-IREF)") (class "Default")
      (node (ref "R8") (pin "P$1") (pinfunction "P$1_P$1") (pintype "passive"))
      (node (ref "U4") (pin "31") (pinfunction "IREF_31") (pintype "bidirectional"))
    )
    (net (code "70") (name "V+") (class "Default")
      (node (ref "D1") (pin "ANODE") (pinfunction "ANODE_ANODE") (pintype "bidirectional"))
      (node (ref "J1") (pin "P$2") (pinfunction "PIN0_P$2") (pintype "bidirectional"))
      (node (ref "J13") (pin "P$1") (pinfunction "PIN0_P$1") (pintype "bidirectional"))
      (node (ref "J14") (pin "P$1") (pinfunction "PIN0_P$1") (pintype "bidirectional"))
      (node (ref "J3") (pin "P$1") (pinfunction "PIN0_P$1") (pintype "bidirectional"))
    )
    (net (code "71") (name "VUSB") (class "Default")
      (node (ref "C7") (pin "P$1") (pinfunction "P$1_P$1") (pintype "passive"))
      (node (ref "C8") (pin "P$1") (pinfunction "P$1_P$1") (pintype "passive"))
      (node (ref "D6") (pin "ANODE") (pinfunction "ANODE_ANODE") (pintype "bidirectional"))
      (node (ref "J4") (pin "1") (pinfunction "5V_1") (pintype "power_in"))
    )
    (net (code "72") (name "unconnected-(J4-ID-Pad4)") (class "Default")
      (node (ref "J4") (pin "4") (pinfunction "ID_4") (pintype "bidirectional"))
    )
    (net (code "73") (name "unconnected-(SW1-PadP$1)") (class "Default")
      (node (ref "SW1") (pin "P$1") (pinfunction "P$1_P$1") (pintype "bidirectional"))
    )
    (net (code "74") (name "unconnected-(SW1-PadP$3)") (class "Default")
      (node (ref "SW1") (pin "P$3") (pinfunction "P$3_P$3") (pintype "bidirectional"))
    )
    (net (code "75") (name "unconnected-(U3-CBUS2-PadP$13)") (class "Default")
      (node (ref "U3") (pin "P$13") (pinfunction "CBUS2_P$13") (pintype "bidirectional"))
    )
    (net (code "76") (name "unconnected-(U3-CBUS3-PadP$14)") (class "Default")
      (node (ref "U3") (pin "P$14") (pinfunction "CBUS3_P$14") (pintype "bidirectional"))
    )
    (net (code "77") (name "unconnected-(U3-CBUS4-PadP$12)") (class "Default")
      (node (ref "U3") (pin "P$12") (pinfunction "CBUS4_P$12") (pintype "bidirectional"))
    )
    (net (code "78") (name "unconnected-(U3-OSCI-PadP$27)") (class "Default")
      (node (ref "U3") (pin "P$27") (pinfunction "OSCI_P$27") (pintype "bidirectional"))
    )
    (net (code "79") (name "unconnected-(U3-OSCO-PadP$28)") (class "Default")
      (node (ref "U3") (pin "P$28") (pinfunction "OSCO_P$28") (pintype "bidirectional"))
    )
    (net (code "80") (name "unconnected-(U3-TEST-PadP$26)") (class "Default")
      (node (ref "U3") (pin "P$26") (pinfunction "TEST_P$26") (pintype "bidirectional"))
    )
    (net (code "81") (name "unconnected-(U3-~{CTS}-PadP$11)") (class "Default")
      (node (ref "U3") (pin "P$11") (pinfunction "~{CTS}_P$11") (pintype "bidirectional"))
    )
    (net (code "82") (name "unconnected-(U3-~{DCD}-PadP$10)") (class "Default")
      (node (ref "U3") (pin "P$10") (pinfunction "~{DCD}_P$10") (pintype "bidirectional"))
    )
    (net (code "83") (name "unconnected-(U3-~{DSR}-PadP$9)") (class "Default")
      (node (ref "U3") (pin "P$9") (pinfunction "~{DSR}_P$9") (pintype "bidirectional"))
    )
    (net (code "84") (name "unconnected-(U3-~{DTR}-PadP$2)") (class "Default")
      (node (ref "U3") (pin "P$2") (pinfunction "~{DTR}_P$2") (pintype "bidirectional"))
    )
    (net (code "85") (name "unconnected-(U3-~{RI}-PadP$6)") (class "Default")
      (node (ref "U3") (pin "P$6") (pinfunction "~{RI}_P$6") (pintype "bidirectional"))
    )
    (net (code "86") (name "unconnected-(U3-~{RTS}-PadP$3)") (class "Default")
      (node (ref "U3") (pin "P$3") (pinfunction "~{RTS}_P$3") (pintype "bidirectional"))
    )
  )
)
